# 05-TYPEC_MUX_USB2.net
KiCad netlist of a schematic drawn in Altium Designer
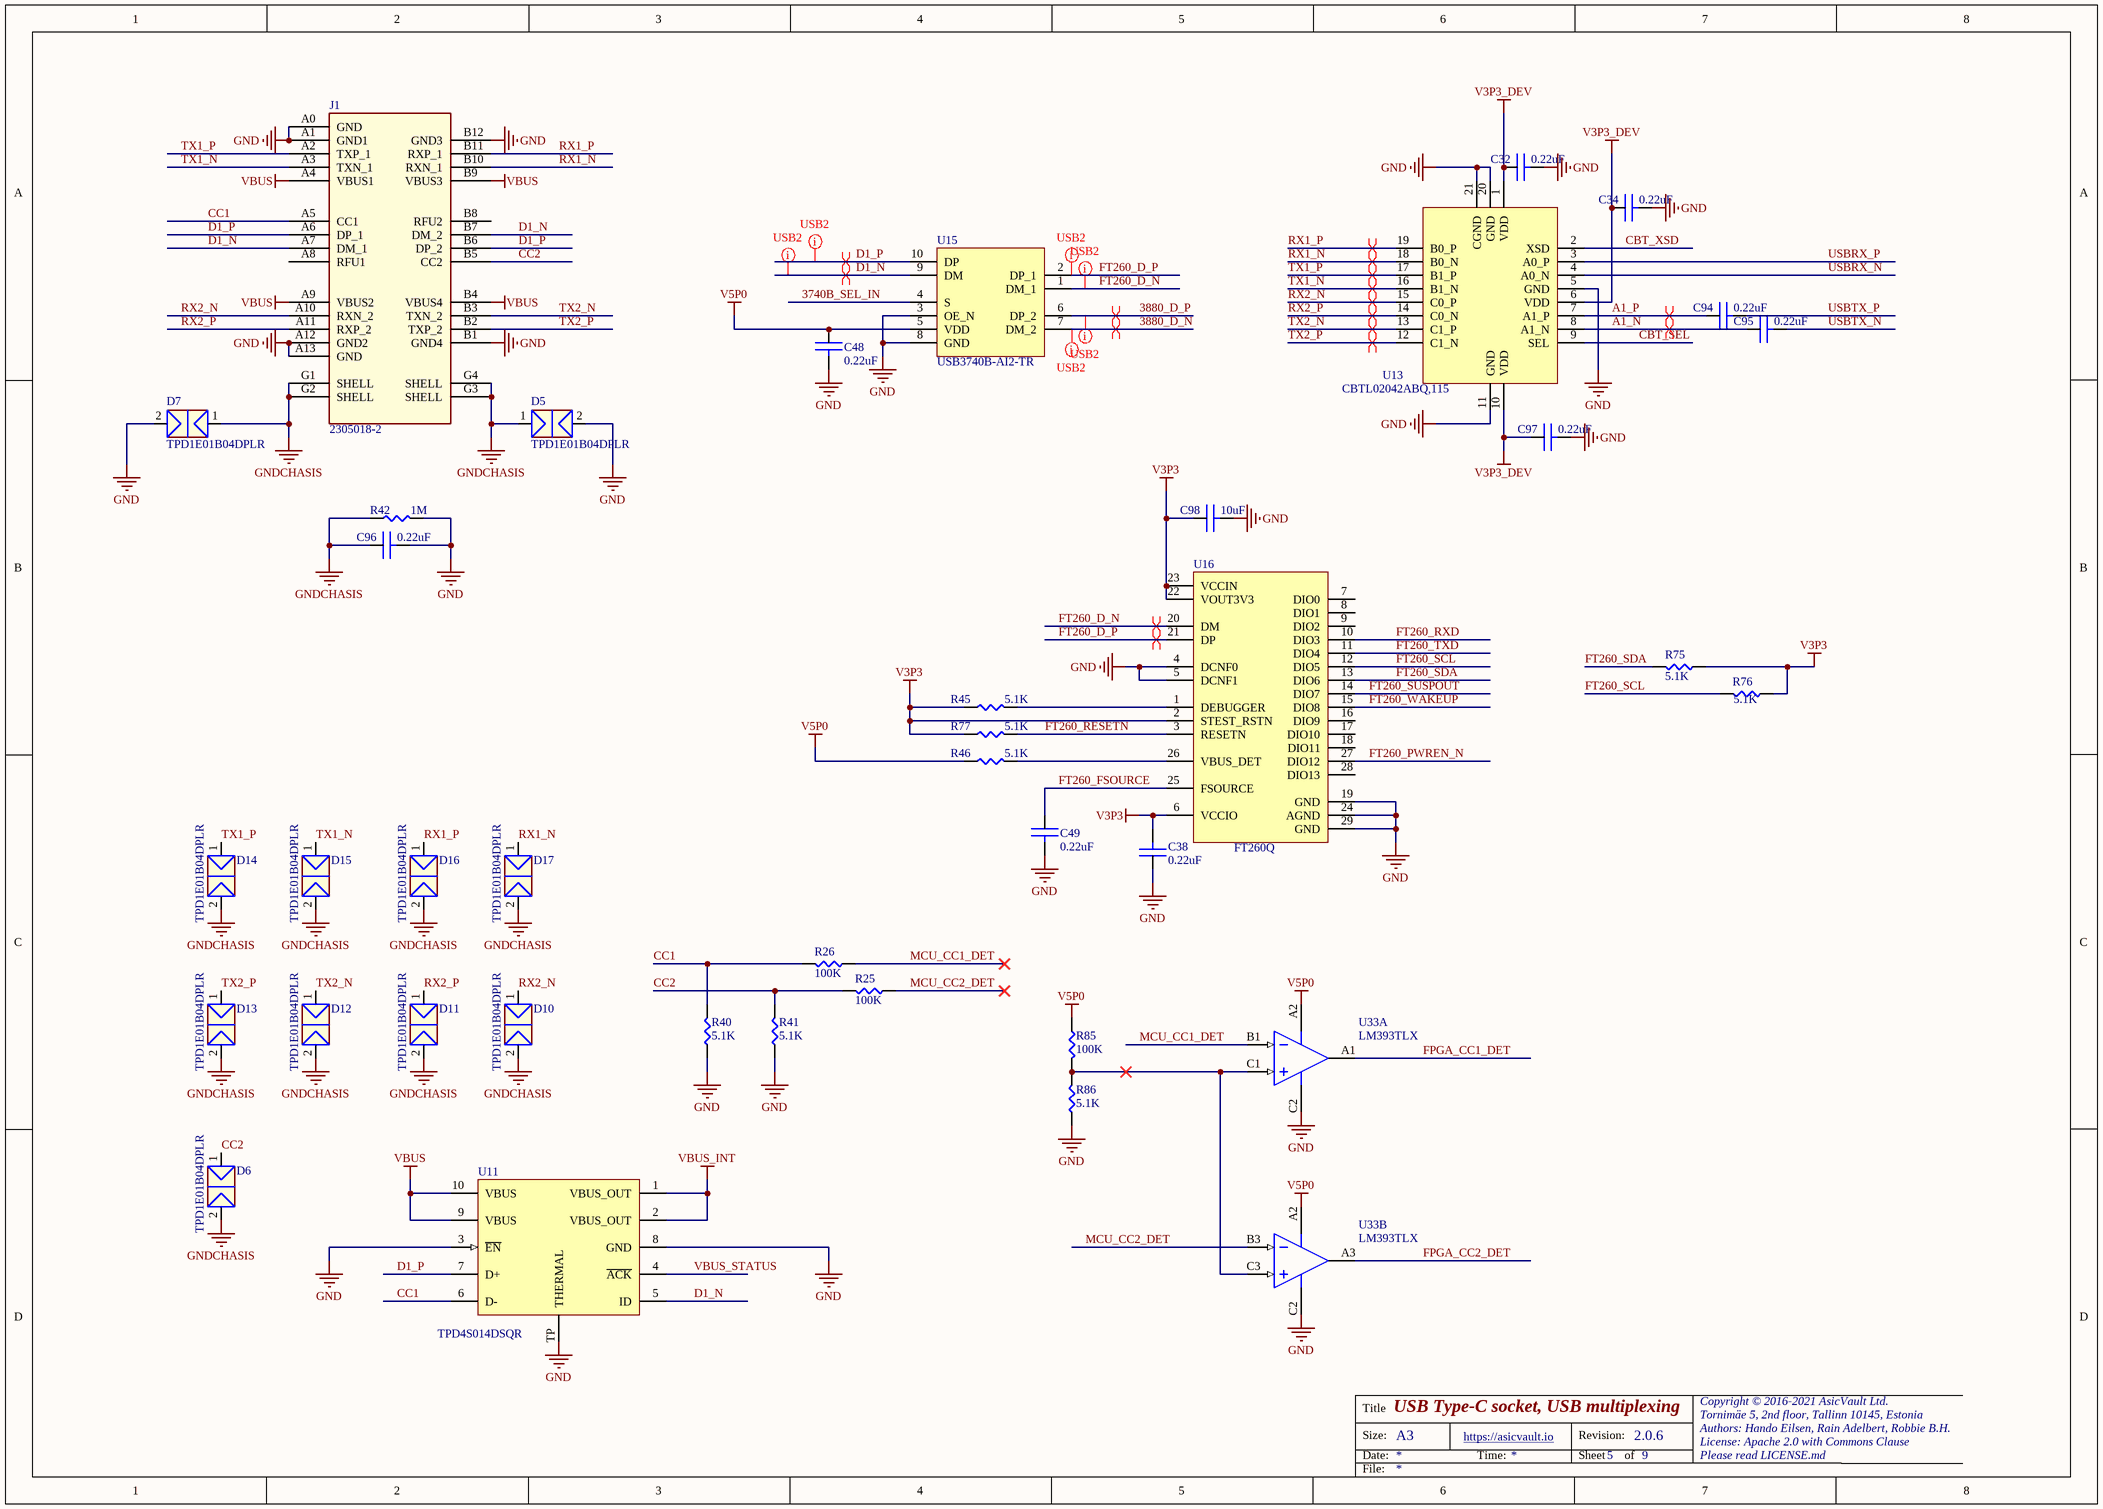
[diagram p0: 05-TYPEC_MUX_USB2.SchDoc]

(export (version "E")
  (design (tool "Eeschema 10.0.6"))
  (components
    (comp (ref "C32") (value "0.22uF") (footprint "C0201") (libsource (lib "AMOLED") (part "0.22uF/0201")))
    (comp (ref "C34") (value "0.22uF") (footprint "C0201") (libsource (lib "AMOLED") (part "0.22uF/0201")))
    (comp (ref "C38") (value "0.22uF") (footprint "C0201") (libsource (lib "AMOLED") (part "0.22uF/0201")))
    (comp (ref "C48") (value "0.22uF") (footprint "C0201") (libsource (lib "AMOLED") (part "0.22uF/0201")))
    (comp (ref "C49") (value "0.22uF") (footprint "C0201") (libsource (lib "AMOLED") (part "0.22uF/0201")))
    (comp (ref "C94") (value "0.22uF") (footprint "C0201") (libsource (lib "AMOLED") (part "0.22uF/0201")))
    (comp (ref "C95") (value "0.22uF") (footprint "C0201") (libsource (lib "AMOLED") (part "0.22uF/0201")))
    (comp (ref "C96") (value "0.22uF") (footprint "C0201") (libsource (lib "AMOLED") (part "0.22uF/0201")))
    (comp (ref "C97") (value "0.22uF") (footprint "C0201") (libsource (lib "AMOLED") (part "0.22uF/0201")))
    (comp (ref "C98") (value "10uF") (footprint "C0402") (libsource (lib "AMOLED") (part "10uF/0402")))
    (comp (ref "D5")
      (value "TPD1E01B04DPLR")
      (footprint "X2XON2")
      (libsource (lib "") (part "TPD1E01B04DPLR_1"))
    )
    (comp (ref "D6")
      (value "TPD1E01B04DPLR")
      (footprint "X2XON2")
      (libsource (lib "Board3") (part "TPD1E01B04DPLR"))
    )
    (comp (ref "D7")
      (value "TPD1E01B04DPLR")
      (footprint "X2XON2")
      (libsource (lib "") (part "TPD1E01B04DPLR_2"))
    )
    (comp (ref "D10")
      (value "TPD1E01B04DPLR")
      (footprint "X2XON2")
      (libsource (lib "Board3") (part "TPD1E01B04DPLR"))
    )
    (comp (ref "D11")
      (value "TPD1E01B04DPLR")
      (footprint "X2XON2")
      (libsource (lib "Board3") (part "TPD1E01B04DPLR"))
    )
    (comp (ref "D12")
      (value "TPD1E01B04DPLR")
      (footprint "X2XON2")
      (libsource (lib "Board3") (part "TPD1E01B04DPLR"))
    )
    (comp (ref "D13")
      (value "TPD1E01B04DPLR")
      (footprint "X2XON2")
      (libsource (lib "Board3") (part "TPD1E01B04DPLR"))
    )
    (comp (ref "D14")
      (value "TPD1E01B04DPLR")
      (footprint "X2XON2")
      (libsource (lib "Board3") (part "TPD1E01B04DPLR"))
    )
    (comp (ref "D15")
      (value "TPD1E01B04DPLR")
      (footprint "X2XON2")
      (libsource (lib "Board3") (part "TPD1E01B04DPLR"))
    )
    (comp (ref "D16")
      (value "TPD1E01B04DPLR")
      (footprint "X2XON2")
      (libsource (lib "Board3") (part "TPD1E01B04DPLR"))
    )
    (comp (ref "D17")
      (value "TPD1E01B04DPLR")
      (footprint "X2XON2")
      (libsource (lib "Board3") (part "TPD1E01B04DPLR"))
    )
    (comp (ref "J1")
      (value "2305018-2")
      (footprint "2305018-2")
      (description "USB TYPE C, REC IPX8 ON BOARD DUAL SMT")
      (libsource (lib "PSD_V2_Schlib") (part "2305018-2"))
    )
    (comp (ref "R25")
      (value "100K")
      (footprint "R0201")
      (libsource (lib "Control_Board") (part "100K/1%/0201"))
    )
    (comp (ref "R26")
      (value "100K")
      (footprint "R0201")
      (libsource (lib "Control_Board") (part "100K/1%/0201"))
    )
    (comp (ref "R40")
      (value "5.1K")
      (footprint "R0201")
      (libsource (lib "Control_Board") (part "5.1K/1%/0201"))
    )
    (comp (ref "R41")
      (value "5.1K")
      (footprint "R0201")
      (libsource (lib "Control_Board") (part "5.1K/1%/0201"))
    )
    (comp (ref "R42") (value "1M") (footprint "R0402") (libsource (lib "Control_Board") (part "1M/1%/0402")))
    (comp (ref "R45")
      (value "5.1K")
      (footprint "R0201")
      (libsource (lib "Control_Board") (part "5.1K/1%/0201"))
    )
    (comp (ref "R46")
      (value "5.1K")
      (footprint "R0201")
      (libsource (lib "Control_Board") (part "5.1K/1%/0201"))
    )
    (comp (ref "R75")
      (value "5.1K")
      (footprint "R0201")
      (libsource (lib "Control_Board") (part "5.1K/1%/0201"))
    )
    (comp (ref "R76")
      (value "5.1K")
      (footprint "R0201")
      (libsource (lib "Control_Board") (part "5.1K/1%/0201"))
    )
    (comp (ref "R77")
      (value "5.1K")
      (footprint "R0201")
      (libsource (lib "Control_Board") (part "5.1K/1%/0201"))
    )
    (comp (ref "R85")
      (value "100K")
      (footprint "R0201")
      (libsource (lib "Control_Board") (part "100K/1%/0201"))
    )
    (comp (ref "R86")
      (value "5.1K")
      (footprint "R0201")
      (libsource (lib "Control_Board") (part "5.1K/1%/0201"))
    )
    (comp (ref "U11")
      (value "TPD4S014DSQR")
      (footprint "R-PWSON-N10")
      (description "Haptic Drive for ERM and LRA")
      (libsource (lib "PSD_V2_Schlib") (part "TPD4S014DSQR"))
    )
    (comp (ref "U13")
      (value "CBTL02042ABQ,115")
      (footprint "DHVQFN20P")
      (libsource (lib "AMOLED") (part "CBTL02042ABQ,115"))
    )
    (comp (ref "U15")
      (value "USB3740B-AI2-TR")
      (footprint "QFN10_1318")
      (libsource (lib "AMOLED") (part "USB3740B-AI2-TR"))
    )
    (comp (ref "U16") (value "FT260Q") (footprint "WQFN28") (libsource (lib "AMOLED") (part "FT260Q")))
    (comp (ref "U33")
      (value "LM393TLX")
      (footprint "DSBGA8x3")
      (description "Dual Voltage Comparator")
      (libsource (lib "PSD_V2_Schlib") (part "LM393TLX"))
    )
  )
  (nets
    (net (code "1") (name "/3740B_SEL_IN") (class "Default")
      (node (ref "U15") (pin "4") (pinfunction "S_4") (pintype "passive"))
    )
    (net (code "2") (name "/3880_D_N") (class "Default")
      (node (ref "U15") (pin "7") (pinfunction "DM_2_7") (pintype "passive"))
    )
    (net (code "3") (name "/3880_D_P") (class "Default")
      (node (ref "U15") (pin "6") (pinfunction "DP_2_6") (pintype "passive"))
    )
    (net (code "4") (name "/A1_N") (class "Default")
      (node (ref "C95") (pin "1") (pinfunction "1_1") (pintype "passive"))
      (node (ref "U13") (pin "8") (pinfunction "A1_N_8") (pintype "passive"))
    )
    (net (code "5") (name "/A1_P") (class "Default")
      (node (ref "C94") (pin "1") (pinfunction "1_1") (pintype "passive"))
      (node (ref "U13") (pin "7") (pinfunction "A1_P_7") (pintype "passive"))
    )
    (net (code "6") (name "/CBT_SEL") (class "Default")
      (node (ref "U13") (pin "9") (pinfunction "SEL_9") (pintype "passive"))
    )
    (net (code "7") (name "/CBT_XSD") (class "Default")
      (node (ref "U13") (pin "2") (pinfunction "XSD_2") (pintype "passive"))
    )
    (net (code "8") (name "/CC1") (class "Default")
      (node (ref "J1") (pin "A5") (pinfunction "CC1_A5") (pintype "passive"))
      (node (ref "R26") (pin "2") (pinfunction "2_2") (pintype "passive"))
      (node (ref "R40") (pin "2") (pinfunction "2_2") (pintype "passive"))
      (node (ref "U11") (pin "6") (pinfunction "D-_6") (pintype "power_in"))
    )
    (net (code "9") (name "/CC2") (class "Default")
      (node (ref "D6") (pin "1") (pinfunction "A_1") (pintype "passive"))
      (node (ref "J1") (pin "B5") (pinfunction "CC2_B5") (pintype "passive"))
      (node (ref "R25") (pin "2") (pinfunction "2_2") (pintype "passive"))
      (node (ref "R41") (pin "2") (pinfunction "2_2") (pintype "passive"))
    )
    (net (code "10") (name "/D1_N") (class "Default")
      (node (ref "J1") (pin "A7") (pinfunction "DM_1_A7") (pintype "passive"))
      (node (ref "J1") (pin "B7") (pinfunction "DM_2_B7") (pintype "passive"))
      (node (ref "U11") (pin "5") (pinfunction "ID_5") (pintype "passive"))
      (node (ref "U15") (pin "9") (pinfunction "DM_9") (pintype "passive"))
    )
    (net (code "11") (name "/D1_P") (class "Default")
      (node (ref "J1") (pin "A6") (pinfunction "DP_1_A6") (pintype "passive"))
      (node (ref "J1") (pin "B6") (pinfunction "DP_2_B6") (pintype "passive"))
      (node (ref "U11") (pin "7") (pinfunction "D+_7") (pintype "passive"))
      (node (ref "U15") (pin "10") (pinfunction "DP_10") (pintype "passive"))
    )
    (net (code "12") (name "/FPGA_CC1_DET") (class "Default")
      (node (ref "U33") (pin "A1") (pinfunction "OUT_A1") (pintype "open_collector"))
    )
    (net (code "13") (name "/FPGA_CC2_DET") (class "Default")
      (node (ref "U33") (pin "A3") (pinfunction "OUT_A3") (pintype "open_collector"))
    )
    (net (code "14") (name "/FT260_D_N") (class "Default")
      (node (ref "U15") (pin "1") (pinfunction "DM_1_1") (pintype "passive"))
      (node (ref "U16") (pin "20") (pinfunction "DM_20") (pintype "passive"))
    )
    (net (code "15") (name "/FT260_D_P") (class "Default")
      (node (ref "U15") (pin "2") (pinfunction "DP_1_2") (pintype "passive"))
      (node (ref "U16") (pin "21") (pinfunction "DP_21") (pintype "passive"))
    )
    (net (code "16") (name "/FT260_FSOURCE") (class "Default")
      (node (ref "C49") (pin "1") (pinfunction "1_1") (pintype "passive"))
      (node (ref "U16") (pin "25") (pinfunction "FSOURCE_25") (pintype "passive"))
    )
    (net (code "17") (name "/FT260_PWREN_N") (class "Default")
      (node (ref "U16") (pin "27") (pinfunction "DIO12_27") (pintype "passive"))
    )
    (net (code "18") (name "/FT260_RESETN") (class "Default")
      (node (ref "R77") (pin "2") (pinfunction "2_2") (pintype "passive"))
      (node (ref "U16") (pin "3") (pinfunction "RESETN_3") (pintype "passive"))
    )
    (net (code "19") (name "/FT260_RXD") (class "Default")
      (node (ref "U16") (pin "10") (pinfunction "DIO3_10") (pintype "passive"))
    )
    (net (code "20") (name "/FT260_SCL") (class "Default")
      (node (ref "R76") (pin "1") (pinfunction "1_1") (pintype "passive"))
      (node (ref "U16") (pin "12") (pinfunction "DIO5_12") (pintype "passive"))
    )
    (net (code "21") (name "/FT260_SDA") (class "Default")
      (node (ref "R75") (pin "1") (pinfunction "1_1") (pintype "passive"))
      (node (ref "U16") (pin "13") (pinfunction "DIO6_13") (pintype "passive"))
    )
    (net (code "22") (name "/FT260_SUSPOUT") (class "Default")
      (node (ref "U16") (pin "14") (pinfunction "DIO7_14") (pintype "passive"))
    )
    (net (code "23") (name "/FT260_TXD") (class "Default")
      (node (ref "U16") (pin "11") (pinfunction "DIO4_11") (pintype "passive"))
    )
    (net (code "24") (name "/FT260_WAKEUP") (class "Default")
      (node (ref "U16") (pin "15") (pinfunction "DIO8_15") (pintype "passive"))
    )
    (net (code "25") (name "/MCU_CC1_DET") (class "Default")
      (node (ref "R26") (pin "1") (pinfunction "1_1") (pintype "passive"))
      (node (ref "U33") (pin "B1") (pinfunction "IN-_B1") (pintype "input"))
    )
    (net (code "26") (name "/MCU_CC2_DET") (class "Default")
      (node (ref "R25") (pin "1") (pinfunction "1_1") (pintype "passive"))
      (node (ref "U33") (pin "B3") (pinfunction "IN-_B3") (pintype "input"))
    )
    (net (code "27") (name "/RX1_N") (class "Default")
      (node (ref "D17") (pin "1") (pinfunction "A_1") (pintype "passive"))
      (node (ref "J1") (pin "B10") (pinfunction "RXN_1_B10") (pintype "passive"))
      (node (ref "U13") (pin "18") (pinfunction "B0_N_18") (pintype "passive"))
    )
    (net (code "28") (name "/RX1_P") (class "Default")
      (node (ref "D16") (pin "1") (pinfunction "A_1") (pintype "passive"))
      (node (ref "J1") (pin "B11") (pinfunction "RXP_1_B11") (pintype "passive"))
      (node (ref "U13") (pin "19") (pinfunction "B0_P_19") (pintype "passive"))
    )
    (net (code "29") (name "/RX2_N") (class "Default")
      (node (ref "D10") (pin "1") (pinfunction "A_1") (pintype "passive"))
      (node (ref "J1") (pin "A10") (pinfunction "RXN_2_A10") (pintype "passive"))
      (node (ref "U13") (pin "15") (pinfunction "C0_P_15") (pintype "passive"))
    )
    (net (code "30") (name "/RX2_P") (class "Default")
      (node (ref "D11") (pin "1") (pinfunction "A_1") (pintype "passive"))
      (node (ref "J1") (pin "A11") (pinfunction "RXP_2_A11") (pintype "passive"))
      (node (ref "U13") (pin "14") (pinfunction "C0_N_14") (pintype "passive"))
    )
    (net (code "31") (name "/TX1_N") (class "Default")
      (node (ref "D15") (pin "1") (pinfunction "A_1") (pintype "passive"))
      (node (ref "J1") (pin "A3") (pinfunction "TXN_1_A3") (pintype "passive"))
      (node (ref "U13") (pin "16") (pinfunction "B1_N_16") (pintype "passive"))
    )
    (net (code "32") (name "/TX1_P") (class "Default")
      (node (ref "D14") (pin "1") (pinfunction "A_1") (pintype "passive"))
      (node (ref "J1") (pin "A2") (pinfunction "TXP_1_A2") (pintype "passive"))
      (node (ref "U13") (pin "17") (pinfunction "B1_P_17") (pintype "passive"))
    )
    (net (code "33") (name "/TX2_N") (class "Default")
      (node (ref "D12") (pin "1") (pinfunction "A_1") (pintype "passive"))
      (node (ref "J1") (pin "B3") (pinfunction "TXN_2_B3") (pintype "passive"))
      (node (ref "U13") (pin "13") (pinfunction "C1_P_13") (pintype "passive"))
    )
    (net (code "34") (name "/TX2_P") (class "Default")
      (node (ref "D13") (pin "1") (pinfunction "A_1") (pintype "passive"))
      (node (ref "J1") (pin "B2") (pinfunction "TXP_2_B2") (pintype "passive"))
      (node (ref "U13") (pin "12") (pinfunction "C1_N_12") (pintype "passive"))
    )
    (net (code "35") (name "/USBRX_N") (class "Default")
      (node (ref "U13") (pin "4") (pinfunction "A0_N_4") (pintype "passive"))
    )
    (net (code "36") (name "/USBRX_P") (class "Default")
      (node (ref "U13") (pin "3") (pinfunction "A0_P_3") (pintype "passive"))
    )
    (net (code "37") (name "/USBTX_N") (class "Default")
      (node (ref "C95") (pin "2") (pinfunction "2_2") (pintype "passive"))
    )
    (net (code "38") (name "/USBTX_P") (class "Default")
      (node (ref "C94") (pin "2") (pinfunction "2_2") (pintype "passive"))
    )
    (net (code "39") (name "/VBUS_STATUS") (class "Default")
      (node (ref "U11") (pin "4") (pinfunction "~{ACK}_4") (pintype "open_collector"))
    )
    (net (code "40") (name "GND") (class "Default")
      (node (ref "C32") (pin "2") (pinfunction "2_2") (pintype "passive"))
      (node (ref "C34") (pin "2") (pinfunction "2_2") (pintype "passive"))
      (node (ref "C38") (pin "1") (pinfunction "1_1") (pintype "passive"))
      (node (ref "C48") (pin "2") (pinfunction "2_2") (pintype "passive"))
      (node (ref "C49") (pin "2") (pinfunction "2_2") (pintype "passive"))
      (node (ref "C96") (pin "2") (pinfunction "2_2") (pintype "passive"))
      (node (ref "C97") (pin "2") (pinfunction "2_2") (pintype "passive"))
      (node (ref "C98") (pin "2") (pinfunction "2_2") (pintype "passive"))
      (node (ref "D5") (pin "2") (pinfunction "K_2") (pintype "passive"))
      (node (ref "D7") (pin "2") (pinfunction "K_2") (pintype "passive"))
      (node (ref "J1") (pin "A0") (pinfunction "GND_A0") (pintype "passive"))
      (node (ref "J1") (pin "A1") (pinfunction "GND1_A1") (pintype "passive"))
      (node (ref "J1") (pin "A12") (pinfunction "GND2_A12") (pintype "passive"))
      (node (ref "J1") (pin "A13") (pinfunction "GND_A13") (pintype "passive"))
      (node (ref "J1") (pin "B1") (pinfunction "GND4_B1") (pintype "passive"))
      (node (ref "J1") (pin "B12") (pinfunction "GND3_B12") (pintype "passive"))
      (node (ref "R40") (pin "1") (pinfunction "1_1") (pintype "passive"))
      (node (ref "R41") (pin "1") (pinfunction "1_1") (pintype "passive"))
      (node (ref "R42") (pin "2") (pinfunction "2_2") (pintype "passive"))
      (node (ref "R86") (pin "1") (pinfunction "1_1") (pintype "passive"))
      (node (ref "U11") (pin "3") (pinfunction "~{EN}_3") (pintype "input"))
      (node (ref "U11") (pin "8") (pinfunction "GND_8") (pintype "power_in"))
      (node (ref "U11") (pin "TP") (pinfunction "THERMAL_TP") (pintype "passive"))
      (node (ref "U13") (pin "11") (pinfunction "GND_11") (pintype "passive"))
      (node (ref "U13") (pin "20") (pinfunction "GND_20") (pintype "passive"))
      (node (ref "U13") (pin "21") (pinfunction "CGND_21") (pintype "passive"))
      (node (ref "U13") (pin "5") (pinfunction "GND_5") (pintype "passive"))
      (node (ref "U15") (pin "3") (pinfunction "OE_N_3") (pintype "passive"))
      (node (ref "U15") (pin "8") (pinfunction "GND_8") (pintype "passive"))
      (node (ref "U16") (pin "19") (pinfunction "GND_19") (pintype "passive"))
      (node (ref "U16") (pin "24") (pinfunction "AGND_24") (pintype "passive"))
      (node (ref "U16") (pin "29") (pinfunction "GND_29") (pintype "passive"))
      (node (ref "U16") (pin "4") (pinfunction "DCNF0_4") (pintype "passive"))
      (node (ref "U16") (pin "5") (pinfunction "DCNF1_5") (pintype "passive"))
      (node (ref "U33") (pin "C2") (pinfunction "GND_C2") (pintype "power_in"))
    )
    (net (code "41") (name "GNDCHASIS") (class "Default")
      (node (ref "C96") (pin "1") (pinfunction "1_1") (pintype "passive"))
      (node (ref "D10") (pin "2") (pinfunction "K_2") (pintype "passive"))
      (node (ref "D11") (pin "2") (pinfunction "K_2") (pintype "passive"))
      (node (ref "D12") (pin "2") (pinfunction "K_2") (pintype "passive"))
      (node (ref "D13") (pin "2") (pinfunction "K_2") (pintype "passive"))
      (node (ref "D14") (pin "2") (pinfunction "K_2") (pintype "passive"))
      (node (ref "D15") (pin "2") (pinfunction "K_2") (pintype "passive"))
      (node (ref "D16") (pin "2") (pinfunction "K_2") (pintype "passive"))
      (node (ref "D17") (pin "2") (pinfunction "K_2") (pintype "passive"))
      (node (ref "D5") (pin "1") (pinfunction "A_1") (pintype "passive"))
      (node (ref "D6") (pin "2") (pinfunction "K_2") (pintype "passive"))
      (node (ref "D7") (pin "1") (pinfunction "A_1") (pintype "passive"))
      (node (ref "J1") (pin "G1") (pinfunction "SHELL_G1") (pintype "passive"))
      (node (ref "J1") (pin "G2") (pinfunction "SHELL_G2") (pintype "passive"))
      (node (ref "J1") (pin "G3") (pinfunction "SHELL_G3") (pintype "passive"))
      (node (ref "J1") (pin "G4") (pinfunction "SHELL_G4") (pintype "passive"))
      (node (ref "R42") (pin "1") (pinfunction "1_1") (pintype "passive"))
    )
    (net (code "42") (name "Net-(U16-DEBUGGER)") (class "Default")
      (node (ref "R45") (pin "2") (pinfunction "2_2") (pintype "passive"))
      (node (ref "U16") (pin "1") (pinfunction "DEBUGGER_1") (pintype "passive"))
    )
    (net (code "43") (name "Net-(U16-VBUS_DET)") (class "Default")
      (node (ref "R46") (pin "2") (pinfunction "2_2") (pintype "passive"))
      (node (ref "U16") (pin "26") (pinfunction "VBUS_DET_26") (pintype "passive"))
    )
    (net (code "44") (name "Net-(U33A-IN+)") (class "Default")
      (node (ref "R85") (pin "2") (pinfunction "2_2") (pintype "passive"))
      (node (ref "R86") (pin "2") (pinfunction "2_2") (pintype "passive"))
      (node (ref "U33") (pin "C1") (pinfunction "IN+_C1") (pintype "input"))
      (node (ref "U33") (pin "C3") (pinfunction "IN+_C3") (pintype "input"))
    )
    (net (code "45") (name "V3P3") (class "Default")
      (node (ref "C38") (pin "2") (pinfunction "2_2") (pintype "passive"))
      (node (ref "C98") (pin "1") (pinfunction "1_1") (pintype "passive"))
      (node (ref "R45") (pin "1") (pinfunction "1_1") (pintype "passive"))
      (node (ref "R75") (pin "2") (pinfunction "2_2") (pintype "passive"))
      (node (ref "R76") (pin "2") (pinfunction "2_2") (pintype "passive"))
      (node (ref "R77") (pin "1") (pinfunction "1_1") (pintype "passive"))
      (node (ref "U16") (pin "2") (pinfunction "STEST_RSTN_2") (pintype "passive"))
      (node (ref "U16") (pin "22") (pinfunction "VOUT3V3_22") (pintype "passive"))
      (node (ref "U16") (pin "23") (pinfunction "VCCIN_23") (pintype "passive"))
      (node (ref "U16") (pin "6") (pinfunction "VCCIO_6") (pintype "passive"))
    )
    (net (code "46") (name "V3P3_DEV") (class "Default")
      (node (ref "C32") (pin "1") (pinfunction "1_1") (pintype "passive"))
      (node (ref "C34") (pin "1") (pinfunction "1_1") (pintype "passive"))
      (node (ref "C97") (pin "1") (pinfunction "1_1") (pintype "passive"))
      (node (ref "U13") (pin "1") (pinfunction "VDD_1") (pintype "passive"))
      (node (ref "U13") (pin "10") (pinfunction "VDD_10") (pintype "passive"))
      (node (ref "U13") (pin "6") (pinfunction "VDD_6") (pintype "passive"))
    )
    (net (code "47") (name "V5P0") (class "Default")
      (node (ref "C48") (pin "1") (pinfunction "1_1") (pintype "passive"))
      (node (ref "R46") (pin "1") (pinfunction "1_1") (pintype "passive"))
      (node (ref "R85") (pin "1") (pinfunction "1_1") (pintype "passive"))
      (node (ref "U15") (pin "5") (pinfunction "VDD_5") (pintype "passive"))
      (node (ref "U33") (pin "A2") (pinfunction "V+_A2") (pintype "power_in"))
    )
    (net (code "48") (name "VBUS") (class "Default")
      (node (ref "J1") (pin "A4") (pinfunction "VBUS1_A4") (pintype "passive"))
      (node (ref "J1") (pin "A9") (pinfunction "VBUS2_A9") (pintype "passive"))
      (node (ref "J1") (pin "B4") (pinfunction "VBUS4_B4") (pintype "passive"))
      (node (ref "J1") (pin "B9") (pinfunction "VBUS3_B9") (pintype "passive"))
      (node (ref "U11") (pin "10") (pinfunction "VBUS_10") (pintype "power_in"))
      (node (ref "U11") (pin "9") (pinfunction "VBUS_9") (pintype "power_in"))
    )
    (net (code "49") (name "VBUS_INT") (class "Default")
      (node (ref "U11") (pin "1") (pinfunction "VBUS_OUT_1") (pintype "power_in"))
      (node (ref "U11") (pin "2") (pinfunction "VBUS_OUT_2") (pintype "power_in"))
    )
    (net (code "50") (name "unconnected-(J1-RFU1-PadA8)") (class "Default")
      (node (ref "J1") (pin "A8") (pinfunction "RFU1_A8") (pintype "passive"))
    )
    (net (code "51") (name "unconnected-(J1-RFU2-PadB8)") (class "Default")
      (node (ref "J1") (pin "B8") (pinfunction "RFU2_B8") (pintype "passive"))
    )
    (net (code "52") (name "unconnected-(U16-DIO0-Pad7)") (class "Default")
      (node (ref "U16") (pin "7") (pinfunction "DIO0_7") (pintype "passive"))
    )
    (net (code "53") (name "unconnected-(U16-DIO1-Pad8)") (class "Default")
      (node (ref "U16") (pin "8") (pinfunction "DIO1_8") (pintype "passive"))
    )
    (net (code "54") (name "unconnected-(U16-DIO2-Pad9)") (class "Default")
      (node (ref "U16") (pin "9") (pinfunction "DIO2_9") (pintype "passive"))
    )
    (net (code "55") (name "unconnected-(U16-DIO9-Pad16)") (class "Default")
      (node (ref "U16") (pin "16") (pinfunction "DIO9_16") (pintype "passive"))
    )
    (net (code "56") (name "unconnected-(U16-DIO10-Pad17)") (class "Default")
      (node (ref "U16") (pin "17") (pinfunction "DIO10_17") (pintype "passive"))
    )
    (net (code "57") (name "unconnected-(U16-DIO11-Pad18)") (class "Default")
      (node (ref "U16") (pin "18") (pinfunction "DIO11_18") (pintype "passive"))
    )
    (net (code "58") (name "unconnected-(U16-DIO13-Pad28)") (class "Default")
      (node (ref "U16") (pin "28") (pinfunction "DIO13_28") (pintype "passive"))
    )
  )
)
